# Cowbell.net
KiCad netlist of a schematic drawn in EAGLE
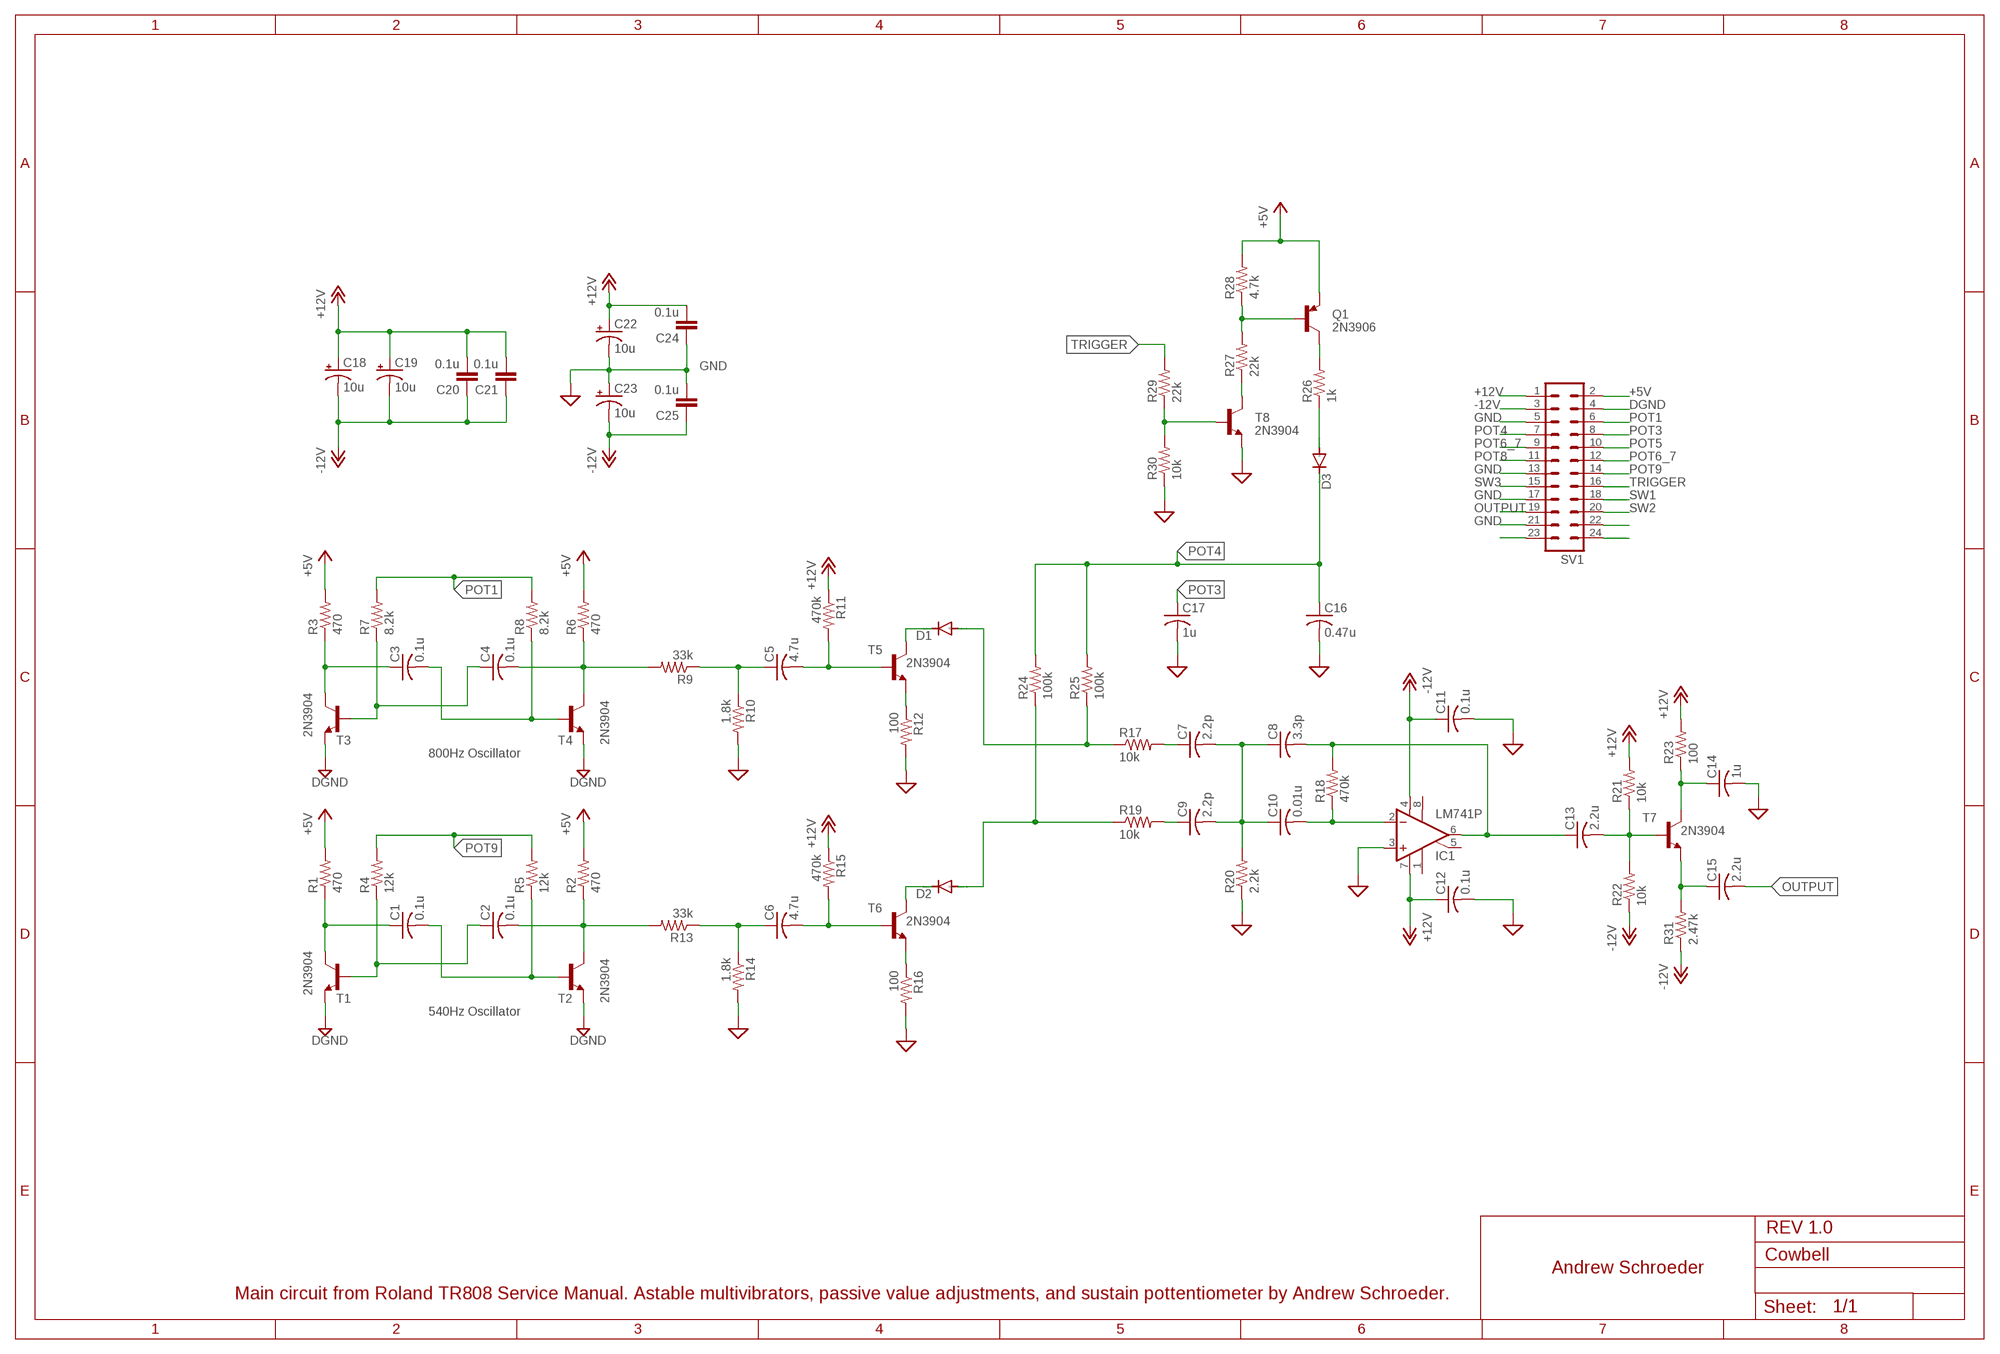
[diagram p0: schematic, sheet 1]

(export (version "E")
  (design (tool "Eeschema 10.0.6"))
  (components
    (comp (ref "C1")
      (value "0.1u")
      (footprint "eagle-import:C025-024X044")
      (libsource (lib "eagle-import") (part "C-US025-024X044"))
    )
    (comp (ref "C2")
      (value "0.1u")
      (footprint "eagle-import:C025-024X044")
      (libsource (lib "eagle-import") (part "C-US025-024X044"))
    )
    (comp (ref "C3")
      (value "0.1u")
      (footprint "eagle-import:C025-024X044")
      (libsource (lib "eagle-import") (part "C-US025-024X044"))
    )
    (comp (ref "C4")
      (value "0.1u")
      (footprint "eagle-import:C025-024X044")
      (libsource (lib "eagle-import") (part "C-US025-024X044"))
    )
    (comp (ref "C5")
      (value "4.7u")
      (footprint "eagle-import:C025-024X044")
      (libsource (lib "eagle-import") (part "C-US025-024X044"))
    )
    (comp (ref "C6")
      (value "4.7u")
      (footprint "eagle-import:C025-024X044")
      (libsource (lib "eagle-import") (part "C-US025-024X044"))
    )
    (comp (ref "C7")
      (value "2.2p")
      (footprint "eagle-import:C025-024X044")
      (libsource (lib "eagle-import") (part "C-US025-024X044"))
    )
    (comp (ref "C8")
      (value "3.3p")
      (footprint "eagle-import:C025-024X044")
      (libsource (lib "eagle-import") (part "C-US025-024X044"))
    )
    (comp (ref "C9")
      (value "2.2p")
      (footprint "eagle-import:C025-024X044")
      (libsource (lib "eagle-import") (part "C-US025-024X044"))
    )
    (comp (ref "C10")
      (value "0.01u")
      (footprint "eagle-import:C025-024X044")
      (libsource (lib "eagle-import") (part "C-US025-024X044"))
    )
    (comp (ref "C11")
      (value "0.1u")
      (footprint "eagle-import:C025-024X044")
      (libsource (lib "eagle-import") (part "C-US025-024X044"))
    )
    (comp (ref "C12")
      (value "0.1u")
      (footprint "eagle-import:C025-024X044")
      (libsource (lib "eagle-import") (part "C-US025-024X044"))
    )
    (comp (ref "C13")
      (value "2.2u")
      (footprint "eagle-import:C025-024X044")
      (libsource (lib "eagle-import") (part "C-US025-024X044"))
    )
    (comp (ref "C14")
      (value "1u")
      (footprint "eagle-import:C025-024X044")
      (libsource (lib "eagle-import") (part "C-US025-024X044"))
    )
    (comp (ref "C15")
      (value "2.2u")
      (footprint "eagle-import:C025-024X044")
      (libsource (lib "eagle-import") (part "C-US025-024X044"))
    )
    (comp (ref "C16")
      (value "0.47u")
      (footprint "eagle-import:C025-024X044")
      (libsource (lib "eagle-import") (part "C-US025-024X044"))
    )
    (comp (ref "C17")
      (value "1u")
      (footprint "eagle-import:C025-024X044")
      (libsource (lib "eagle-import") (part "C-US025-024X044"))
    )
    (comp (ref "C18")
      (value "10u")
      (footprint "eagle-import:E2,5-6")
      (libsource (lib "eagle-import") (part "CPOL-USE2.5-6"))
    )
    (comp (ref "C19")
      (value "10u")
      (footprint "eagle-import:E2,5-6")
      (libsource (lib "eagle-import") (part "CPOL-USE2.5-6"))
    )
    (comp (ref "C20")
      (value "0.1u")
      (footprint "eagle-import:C050-024X044")
      (libsource (lib "eagle-import") (part "C-EU050-024X044"))
    )
    (comp (ref "C21")
      (value "0.1u")
      (footprint "eagle-import:C050-024X044")
      (libsource (lib "eagle-import") (part "C-EU050-024X044"))
    )
    (comp (ref "C22")
      (value "10u")
      (footprint "eagle-import:E2,5-6")
      (libsource (lib "eagle-import") (part "CPOL-USE2.5-6"))
    )
    (comp (ref "C23")
      (value "10u")
      (footprint "eagle-import:E2,5-6")
      (libsource (lib "eagle-import") (part "CPOL-USE2.5-6"))
    )
    (comp (ref "C24")
      (value "0.1u")
      (footprint "eagle-import:C050-024X044")
      (libsource (lib "eagle-import") (part "C-EU050-024X044"))
    )
    (comp (ref "C25")
      (value "0.1u")
      (footprint "eagle-import:C050-024X044")
      (libsource (lib "eagle-import") (part "C-EU050-024X044"))
    )
    (comp (ref "D1")
      (value "1N4148DO35-7")
      (footprint "eagle-import:DO35-7")
      (libsource (lib "eagle-import") (part "1N4148DO35-7"))
    )
    (comp (ref "D2")
      (value "1N4148DO35-7")
      (footprint "eagle-import:DO35-7")
      (libsource (lib "eagle-import") (part "1N4148DO35-7"))
    )
    (comp (ref "D3")
      (value "1N4148DO35-7")
      (footprint "eagle-import:DO35-7")
      (libsource (lib "eagle-import") (part "1N4148DO35-7"))
    )
    (comp (ref "IC1")
      (value "LM741P")
      (footprint "eagle-import:DIL08")
      (libsource (lib "eagle-import") (part "741PLM"))
    )
    (comp (ref "Q1")
      (value "2N3906")
      (footprint "eagle-import:TO92")
      (libsource (lib "eagle-import") (part "2N3906"))
    )
    (comp (ref "R1")
      (value "470")
      (footprint "eagle-import:0207_7")
      (libsource (lib "eagle-import") (part "R-US_0207/7"))
    )
    (comp (ref "R2")
      (value "470")
      (footprint "eagle-import:0207_7")
      (libsource (lib "eagle-import") (part "R-US_0207/7"))
    )
    (comp (ref "R3")
      (value "470")
      (footprint "eagle-import:0207_7")
      (libsource (lib "eagle-import") (part "R-US_0207/7"))
    )
    (comp (ref "R4")
      (value "12k")
      (footprint "eagle-import:0207_7")
      (libsource (lib "eagle-import") (part "R-US_0207/7"))
    )
    (comp (ref "R5")
      (value "12k")
      (footprint "eagle-import:0207_7")
      (libsource (lib "eagle-import") (part "R-US_0207/7"))
    )
    (comp (ref "R6")
      (value "470")
      (footprint "eagle-import:0207_7")
      (libsource (lib "eagle-import") (part "R-US_0207/7"))
    )
    (comp (ref "R7")
      (value "8.2k")
      (footprint "eagle-import:0207_7")
      (libsource (lib "eagle-import") (part "R-US_0207/7"))
    )
    (comp (ref "R8")
      (value "8.2k")
      (footprint "eagle-import:0207_7")
      (libsource (lib "eagle-import") (part "R-US_0207/7"))
    )
    (comp (ref "R9")
      (value "33k")
      (footprint "eagle-import:0207_7")
      (libsource (lib "eagle-import") (part "R-US_0207/7"))
    )
    (comp (ref "R10")
      (value "1.8k")
      (footprint "eagle-import:0207_7")
      (libsource (lib "eagle-import") (part "R-US_0207/7"))
    )
    (comp (ref "R11")
      (value "470k")
      (footprint "eagle-import:0207_7")
      (libsource (lib "eagle-import") (part "R-US_0207/7"))
    )
    (comp (ref "R12")
      (value "100")
      (footprint "eagle-import:0207_7")
      (libsource (lib "eagle-import") (part "R-US_0207/7"))
    )
    (comp (ref "R13")
      (value "33k")
      (footprint "eagle-import:0207_7")
      (libsource (lib "eagle-import") (part "R-US_0207/7"))
    )
    (comp (ref "R14")
      (value "1.8k")
      (footprint "eagle-import:0207_7")
      (libsource (lib "eagle-import") (part "R-US_0207/7"))
    )
    (comp (ref "R15")
      (value "470k")
      (footprint "eagle-import:0207_7")
      (libsource (lib "eagle-import") (part "R-US_0207/7"))
    )
    (comp (ref "R16")
      (value "100")
      (footprint "eagle-import:0207_7")
      (libsource (lib "eagle-import") (part "R-US_0207/7"))
    )
    (comp (ref "R17")
      (value "10k")
      (footprint "eagle-import:0207_7")
      (libsource (lib "eagle-import") (part "R-US_0207/7"))
    )
    (comp (ref "R18")
      (value "470k")
      (footprint "eagle-import:0207_7")
      (libsource (lib "eagle-import") (part "R-US_0207/7"))
    )
    (comp (ref "R19")
      (value "10k")
      (footprint "eagle-import:0207_7")
      (libsource (lib "eagle-import") (part "R-US_0207/7"))
    )
    (comp (ref "R20")
      (value "2.2k")
      (footprint "eagle-import:0207_7")
      (libsource (lib "eagle-import") (part "R-US_0207/7"))
    )
    (comp (ref "R21")
      (value "10k")
      (footprint "eagle-import:0207_7")
      (libsource (lib "eagle-import") (part "R-US_0207/7"))
    )
    (comp (ref "R22")
      (value "10k")
      (footprint "eagle-import:0207_7")
      (libsource (lib "eagle-import") (part "R-US_0207/7"))
    )
    (comp (ref "R23")
      (value "100")
      (footprint "eagle-import:0207_7")
      (libsource (lib "eagle-import") (part "R-US_0207/7"))
    )
    (comp (ref "R24")
      (value "100k")
      (footprint "eagle-import:0207_7")
      (libsource (lib "eagle-import") (part "R-US_0207/7"))
    )
    (comp (ref "R25")
      (value "100k")
      (footprint "eagle-import:0207_7")
      (libsource (lib "eagle-import") (part "R-US_0207/7"))
    )
    (comp (ref "R26")
      (value "1k")
      (footprint "eagle-import:0207_7")
      (libsource (lib "eagle-import") (part "R-US_0207/7"))
    )
    (comp (ref "R27")
      (value "22k")
      (footprint "eagle-import:0207_7")
      (libsource (lib "eagle-import") (part "R-US_0207/7"))
    )
    (comp (ref "R28")
      (value "4.7k")
      (footprint "eagle-import:0207_7")
      (libsource (lib "eagle-import") (part "R-US_0207/7"))
    )
    (comp (ref "R29")
      (value "22k")
      (footprint "eagle-import:0207_7")
      (libsource (lib "eagle-import") (part "R-US_0207/7"))
    )
    (comp (ref "R30")
      (value "10k")
      (footprint "eagle-import:0207_7")
      (libsource (lib "eagle-import") (part "R-US_0207/7"))
    )
    (comp (ref "R31")
      (value "2.47k")
      (footprint "eagle-import:0207_7")
      (libsource (lib "eagle-import") (part "R-US_0207/7"))
    )
    (comp (ref "SV1")
      (value "MA12-2")
      (footprint "eagle-import:MA12-2")
      (libsource (lib "eagle-import") (part "MA12-2"))
    )
    (comp (ref "T1")
      (value "2N3904")
      (footprint "eagle-import:TO92")
      (libsource (lib "eagle-import") (part "2N3904"))
    )
    (comp (ref "T2")
      (value "2N3904")
      (footprint "eagle-import:TO92")
      (libsource (lib "eagle-import") (part "2N3904"))
    )
    (comp (ref "T3")
      (value "2N3904")
      (footprint "eagle-import:TO92")
      (libsource (lib "eagle-import") (part "2N3904"))
    )
    (comp (ref "T4")
      (value "2N3904")
      (footprint "eagle-import:TO92")
      (libsource (lib "eagle-import") (part "2N3904"))
    )
    (comp (ref "T5")
      (value "2N3904")
      (footprint "eagle-import:TO92")
      (libsource (lib "eagle-import") (part "2N3904"))
    )
    (comp (ref "T6")
      (value "2N3904")
      (footprint "eagle-import:TO92")
      (libsource (lib "eagle-import") (part "2N3904"))
    )
    (comp (ref "T7")
      (value "2N3904")
      (footprint "eagle-import:TO92")
      (libsource (lib "eagle-import") (part "2N3904"))
    )
    (comp (ref "T8")
      (value "2N3904")
      (footprint "eagle-import:TO92")
      (libsource (lib "eagle-import") (part "2N3904"))
    )
  )
  (nets
    (net (code "1") (name "+5V") (class "Default")
      (node (ref "Q1") (pin "3") (pinfunction "E_3") (pintype "passive"))
      (node (ref "R1") (pin "2") (pinfunction "2_2") (pintype "passive"))
      (node (ref "R2") (pin "2") (pinfunction "2_2") (pintype "passive"))
      (node (ref "R28") (pin "2") (pinfunction "2_2") (pintype "passive"))
      (node (ref "R3") (pin "2") (pinfunction "2_2") (pintype "passive"))
      (node (ref "R6") (pin "2") (pinfunction "2_2") (pintype "passive"))
      (node (ref "SV1") (pin "2") (pinfunction "2_2") (pintype "passive"))
    )
    (net (code "2") (name "+12V") (class "Default")
      (node (ref "C12") (pin "1") (pinfunction "1_1") (pintype "passive"))
      (node (ref "C18") (pin "+") (pinfunction "+_+") (pintype "passive"))
      (node (ref "C19") (pin "+") (pinfunction "+_+") (pintype "passive"))
      (node (ref "C20") (pin "2") (pinfunction "2_2") (pintype "passive"))
      (node (ref "C21") (pin "2") (pinfunction "2_2") (pintype "passive"))
      (node (ref "C22") (pin "+") (pinfunction "+_+") (pintype "passive"))
      (node (ref "C24") (pin "2") (pinfunction "2_2") (pintype "passive"))
      (node (ref "IC1") (pin "7") (pinfunction "V+_7") (pintype "power_in"))
      (node (ref "R11") (pin "1") (pinfunction "1_1") (pintype "passive"))
      (node (ref "R15") (pin "1") (pinfunction "1_1") (pintype "passive"))
      (node (ref "R21") (pin "2") (pinfunction "2_2") (pintype "passive"))
      (node (ref "R23") (pin "2") (pinfunction "2_2") (pintype "passive"))
      (node (ref "SV1") (pin "1") (pinfunction "1_1") (pintype "passive"))
    )
    (net (code "3") (name "-12V") (class "Default")
      (node (ref "C11") (pin "1") (pinfunction "1_1") (pintype "passive"))
      (node (ref "C18") (pin "-") (pinfunction "-_-") (pintype "passive"))
      (node (ref "C19") (pin "-") (pinfunction "-_-") (pintype "passive"))
      (node (ref "C20") (pin "1") (pinfunction "1_1") (pintype "passive"))
      (node (ref "C21") (pin "1") (pinfunction "1_1") (pintype "passive"))
      (node (ref "C23") (pin "-") (pinfunction "-_-") (pintype "passive"))
      (node (ref "C25") (pin "1") (pinfunction "1_1") (pintype "passive"))
      (node (ref "IC1") (pin "4") (pinfunction "V-_4") (pintype "power_in"))
      (node (ref "R22") (pin "1") (pinfunction "1_1") (pintype "passive"))
      (node (ref "R31") (pin "1") (pinfunction "1_1") (pintype "passive"))
      (node (ref "SV1") (pin "3") (pinfunction "3_3") (pintype "passive"))
    )
    (net (code "4") (name "/POT5") (class "Default")
      (node (ref "SV1") (pin "10") (pinfunction "10_10") (pintype "passive"))
    )
    (net (code "5") (name "/POT6_7") (class "Default")
      (node (ref "SV1") (pin "12") (pinfunction "12_12") (pintype "passive"))
      (node (ref "SV1") (pin "9") (pinfunction "9_9") (pintype "passive"))
    )
    (net (code "6") (name "/POT8") (class "Default")
      (node (ref "SV1") (pin "11") (pinfunction "11_11") (pintype "passive"))
    )
    (net (code "7") (name "/SW1") (class "Default")
      (node (ref "SV1") (pin "18") (pinfunction "18_18") (pintype "passive"))
    )
    (net (code "8") (name "/SW2") (class "Default")
      (node (ref "SV1") (pin "20") (pinfunction "20_20") (pintype "passive"))
    )
    (net (code "9") (name "/SW3") (class "Default")
      (node (ref "SV1") (pin "15") (pinfunction "15_15") (pintype "passive"))
    )
    (net (code "10") (name "DGND") (class "Default")
      (node (ref "SV1") (pin "4") (pinfunction "4_4") (pintype "passive"))
      (node (ref "T1") (pin "3") (pinfunction "E_3") (pintype "passive"))
      (node (ref "T2") (pin "3") (pinfunction "E_3") (pintype "passive"))
      (node (ref "T3") (pin "3") (pinfunction "E_3") (pintype "passive"))
      (node (ref "T4") (pin "3") (pinfunction "E_3") (pintype "passive"))
    )
    (net (code "11") (name "Net-(C5-Pad1)") (class "Default")
      (node (ref "C5") (pin "1") (pinfunction "1_1") (pintype "passive"))
      (node (ref "R10") (pin "1") (pinfunction "1_1") (pintype "passive"))
      (node (ref "R9") (pin "1") (pinfunction "1_1") (pintype "passive"))
    )
    (net (code "12") (name "Net-(C6-Pad1)") (class "Default")
      (node (ref "C6") (pin "1") (pinfunction "1_1") (pintype "passive"))
      (node (ref "R13") (pin "1") (pinfunction "1_1") (pintype "passive"))
      (node (ref "R14") (pin "1") (pinfunction "1_1") (pintype "passive"))
    )
    (net (code "13") (name "Net-(C7-Pad1)") (class "Default")
      (node (ref "C7") (pin "1") (pinfunction "1_1") (pintype "passive"))
      (node (ref "R17") (pin "2") (pinfunction "2_2") (pintype "passive"))
    )
    (net (code "14") (name "Net-(C9-Pad1)") (class "Default")
      (node (ref "C9") (pin "1") (pinfunction "1_1") (pintype "passive"))
      (node (ref "R19") (pin "2") (pinfunction "2_2") (pintype "passive"))
    )
    (net (code "15") (name "Net-(C10-Pad1)") (class "Default")
      (node (ref "C10") (pin "1") (pinfunction "1_1") (pintype "passive"))
      (node (ref "C7") (pin "2") (pinfunction "2_2") (pintype "passive"))
      (node (ref "C8") (pin "1") (pinfunction "1_1") (pintype "passive"))
      (node (ref "C9") (pin "2") (pinfunction "2_2") (pintype "passive"))
      (node (ref "R20") (pin "2") (pinfunction "2_2") (pintype "passive"))
    )
    (net (code "16") (name "Net-(D1-PadA)") (class "Default")
      (node (ref "D1") (pin "A") (pinfunction "A_A") (pintype "passive"))
      (node (ref "R17") (pin "1") (pinfunction "1_1") (pintype "passive"))
      (node (ref "R25") (pin "1") (pinfunction "1_1") (pintype "passive"))
    )
    (net (code "17") (name "Net-(D2-PadA)") (class "Default")
      (node (ref "D2") (pin "A") (pinfunction "A_A") (pintype "passive"))
      (node (ref "R19") (pin "1") (pinfunction "1_1") (pintype "passive"))
      (node (ref "R24") (pin "1") (pinfunction "1_1") (pintype "passive"))
    )
    (net (code "18") (name "Net-(D3-PadA)") (class "Default")
      (node (ref "D3") (pin "A") (pinfunction "A_A") (pintype "passive"))
      (node (ref "R26") (pin "1") (pinfunction "1_1") (pintype "passive"))
    )
    (net (code "19") (name "Net-(IC1--IN)") (class "Default")
      (node (ref "C10") (pin "2") (pinfunction "2_2") (pintype "passive"))
      (node (ref "IC1") (pin "2") (pinfunction "-IN_2") (pintype "input"))
      (node (ref "R18") (pin "1") (pinfunction "1_1") (pintype "passive"))
    )
    (net (code "20") (name "Net-(IC1-OUT)") (class "Default")
      (node (ref "C13") (pin "1") (pinfunction "1_1") (pintype "passive"))
      (node (ref "C8") (pin "2") (pinfunction "2_2") (pintype "passive"))
      (node (ref "IC1") (pin "6") (pinfunction "OUT_6") (pintype "output"))
      (node (ref "R18") (pin "2") (pinfunction "2_2") (pintype "passive"))
    )
    (net (code "21") (name "Net-(Q1-B)") (class "Default")
      (node (ref "Q1") (pin "2") (pinfunction "B_2") (pintype "passive"))
      (node (ref "R27") (pin "2") (pinfunction "2_2") (pintype "passive"))
      (node (ref "R28") (pin "1") (pinfunction "1_1") (pintype "passive"))
    )
    (net (code "22") (name "Net-(Q1-C)") (class "Default")
      (node (ref "Q1") (pin "1") (pinfunction "C_1") (pintype "passive"))
      (node (ref "R26") (pin "2") (pinfunction "2_2") (pintype "passive"))
    )
    (net (code "23") (name "Net-(T1-B)") (class "Default")
      (node (ref "C2") (pin "1") (pinfunction "1_1") (pintype "passive"))
      (node (ref "R4") (pin "1") (pinfunction "1_1") (pintype "passive"))
      (node (ref "T1") (pin "2") (pinfunction "B_2") (pintype "passive"))
    )
    (net (code "24") (name "Net-(T1-C)") (class "Default")
      (node (ref "C1") (pin "1") (pinfunction "1_1") (pintype "passive"))
      (node (ref "R1") (pin "1") (pinfunction "1_1") (pintype "passive"))
      (node (ref "T1") (pin "1") (pinfunction "C_1") (pintype "passive"))
    )
    (net (code "25") (name "Net-(T2-B)") (class "Default")
      (node (ref "C1") (pin "2") (pinfunction "2_2") (pintype "passive"))
      (node (ref "R5") (pin "1") (pinfunction "1_1") (pintype "passive"))
      (node (ref "T2") (pin "2") (pinfunction "B_2") (pintype "passive"))
    )
    (net (code "26") (name "Net-(T2-C)") (class "Default")
      (node (ref "C2") (pin "2") (pinfunction "2_2") (pintype "passive"))
      (node (ref "R13") (pin "2") (pinfunction "2_2") (pintype "passive"))
      (node (ref "R2") (pin "1") (pinfunction "1_1") (pintype "passive"))
      (node (ref "T2") (pin "1") (pinfunction "C_1") (pintype "passive"))
    )
    (net (code "27") (name "Net-(T3-B)") (class "Default")
      (node (ref "C4") (pin "1") (pinfunction "1_1") (pintype "passive"))
      (node (ref "R7") (pin "1") (pinfunction "1_1") (pintype "passive"))
      (node (ref "T3") (pin "2") (pinfunction "B_2") (pintype "passive"))
    )
    (net (code "28") (name "Net-(T3-C)") (class "Default")
      (node (ref "C3") (pin "1") (pinfunction "1_1") (pintype "passive"))
      (node (ref "R3") (pin "1") (pinfunction "1_1") (pintype "passive"))
      (node (ref "T3") (pin "1") (pinfunction "C_1") (pintype "passive"))
    )
    (net (code "29") (name "Net-(T4-B)") (class "Default")
      (node (ref "C3") (pin "2") (pinfunction "2_2") (pintype "passive"))
      (node (ref "R8") (pin "1") (pinfunction "1_1") (pintype "passive"))
      (node (ref "T4") (pin "2") (pinfunction "B_2") (pintype "passive"))
    )
    (net (code "30") (name "Net-(T4-C)") (class "Default")
      (node (ref "C4") (pin "2") (pinfunction "2_2") (pintype "passive"))
      (node (ref "R6") (pin "1") (pinfunction "1_1") (pintype "passive"))
      (node (ref "R9") (pin "2") (pinfunction "2_2") (pintype "passive"))
      (node (ref "T4") (pin "1") (pinfunction "C_1") (pintype "passive"))
    )
    (net (code "31") (name "Net-(T5-B)") (class "Default")
      (node (ref "C5") (pin "2") (pinfunction "2_2") (pintype "passive"))
      (node (ref "R11") (pin "2") (pinfunction "2_2") (pintype "passive"))
      (node (ref "T5") (pin "2") (pinfunction "B_2") (pintype "passive"))
    )
    (net (code "32") (name "Net-(T5-C)") (class "Default")
      (node (ref "D1") (pin "C") (pinfunction "C_C") (pintype "passive"))
      (node (ref "T5") (pin "1") (pinfunction "C_1") (pintype "passive"))
    )
    (net (code "33") (name "Net-(T5-E)") (class "Default")
      (node (ref "R12") (pin "1") (pinfunction "1_1") (pintype "passive"))
      (node (ref "T5") (pin "3") (pinfunction "E_3") (pintype "passive"))
    )
    (net (code "34") (name "Net-(T6-B)") (class "Default")
      (node (ref "C6") (pin "2") (pinfunction "2_2") (pintype "passive"))
      (node (ref "R15") (pin "2") (pinfunction "2_2") (pintype "passive"))
      (node (ref "T6") (pin "2") (pinfunction "B_2") (pintype "passive"))
    )
    (net (code "35") (name "Net-(T6-C)") (class "Default")
      (node (ref "D2") (pin "C") (pinfunction "C_C") (pintype "passive"))
      (node (ref "T6") (pin "1") (pinfunction "C_1") (pintype "passive"))
    )
    (net (code "36") (name "Net-(T6-E)") (class "Default")
      (node (ref "R16") (pin "1") (pinfunction "1_1") (pintype "passive"))
      (node (ref "T6") (pin "3") (pinfunction "E_3") (pintype "passive"))
    )
    (net (code "37") (name "Net-(T7-B)") (class "Default")
      (node (ref "C13") (pin "2") (pinfunction "2_2") (pintype "passive"))
      (node (ref "R21") (pin "1") (pinfunction "1_1") (pintype "passive"))
      (node (ref "R22") (pin "2") (pinfunction "2_2") (pintype "passive"))
      (node (ref "T7") (pin "2") (pinfunction "B_2") (pintype "passive"))
    )
    (net (code "38") (name "Net-(T7-C)") (class "Default")
      (node (ref "C14") (pin "1") (pinfunction "1_1") (pintype "passive"))
      (node (ref "R23") (pin "1") (pinfunction "1_1") (pintype "passive"))
      (node (ref "T7") (pin "1") (pinfunction "C_1") (pintype "passive"))
    )
    (net (code "39") (name "Net-(T7-E)") (class "Default")
      (node (ref "C15") (pin "1") (pinfunction "1_1") (pintype "passive"))
      (node (ref "R31") (pin "2") (pinfunction "2_2") (pintype "passive"))
      (node (ref "T7") (pin "3") (pinfunction "E_3") (pintype "passive"))
    )
    (net (code "40") (name "Net-(T8-B)") (class "Default")
      (node (ref "R29") (pin "1") (pinfunction "1_1") (pintype "passive"))
      (node (ref "R30") (pin "2") (pinfunction "2_2") (pintype "passive"))
      (node (ref "T8") (pin "2") (pinfunction "B_2") (pintype "passive"))
    )
    (net (code "41") (name "Net-(T8-C)") (class "Default")
      (node (ref "R27") (pin "1") (pinfunction "1_1") (pintype "passive"))
      (node (ref "T8") (pin "1") (pinfunction "C_1") (pintype "passive"))
    )
    (net (code "42") (name "OUTPUT") (class "Default")
      (node (ref "C15") (pin "2") (pinfunction "2_2") (pintype "passive"))
      (node (ref "SV1") (pin "19") (pinfunction "19_19") (pintype "passive"))
    )
    (net (code "43") (name "POT1") (class "Default")
      (node (ref "R7") (pin "2") (pinfunction "2_2") (pintype "passive"))
      (node (ref "R8") (pin "2") (pinfunction "2_2") (pintype "passive"))
      (node (ref "SV1") (pin "6") (pinfunction "6_6") (pintype "passive"))
    )
    (net (code "44") (name "POT3") (class "Default")
      (node (ref "C17") (pin "1") (pinfunction "1_1") (pintype "passive"))
      (node (ref "SV1") (pin "8") (pinfunction "8_8") (pintype "passive"))
    )
    (net (code "45") (name "POT4") (class "Default")
      (node (ref "C16") (pin "1") (pinfunction "1_1") (pintype "passive"))
      (node (ref "D3") (pin "C") (pinfunction "C_C") (pintype "passive"))
      (node (ref "R24") (pin "2") (pinfunction "2_2") (pintype "passive"))
      (node (ref "R25") (pin "2") (pinfunction "2_2") (pintype "passive"))
      (node (ref "SV1") (pin "7") (pinfunction "7_7") (pintype "passive"))
    )
    (net (code "46") (name "POT9") (class "Default")
      (node (ref "R4") (pin "2") (pinfunction "2_2") (pintype "passive"))
      (node (ref "R5") (pin "2") (pinfunction "2_2") (pintype "passive"))
      (node (ref "SV1") (pin "14") (pinfunction "14_14") (pintype "passive"))
    )
    (net (code "47") (name "SUP") (class "Default")
      (node (ref "C11") (pin "2") (pinfunction "2_2") (pintype "passive"))
      (node (ref "C12") (pin "2") (pinfunction "2_2") (pintype "passive"))
      (node (ref "C14") (pin "2") (pinfunction "2_2") (pintype "passive"))
      (node (ref "C16") (pin "2") (pinfunction "2_2") (pintype "passive"))
      (node (ref "C17") (pin "2") (pinfunction "2_2") (pintype "passive"))
      (node (ref "C22") (pin "-") (pinfunction "-_-") (pintype "passive"))
      (node (ref "C23") (pin "+") (pinfunction "+_+") (pintype "passive"))
      (node (ref "C24") (pin "1") (pinfunction "1_1") (pintype "passive"))
      (node (ref "C25") (pin "2") (pinfunction "2_2") (pintype "passive"))
      (node (ref "IC1") (pin "3") (pinfunction "+IN_3") (pintype "input"))
      (node (ref "R10") (pin "2") (pinfunction "2_2") (pintype "passive"))
      (node (ref "R12") (pin "2") (pinfunction "2_2") (pintype "passive"))
      (node (ref "R14") (pin "2") (pinfunction "2_2") (pintype "passive"))
      (node (ref "R16") (pin "2") (pinfunction "2_2") (pintype "passive"))
      (node (ref "R20") (pin "1") (pinfunction "1_1") (pintype "passive"))
      (node (ref "R30") (pin "1") (pinfunction "1_1") (pintype "passive"))
      (node (ref "SV1") (pin "13") (pinfunction "13_13") (pintype "passive"))
      (node (ref "SV1") (pin "17") (pinfunction "17_17") (pintype "passive"))
      (node (ref "SV1") (pin "21") (pinfunction "21_21") (pintype "passive"))
      (node (ref "SV1") (pin "5") (pinfunction "5_5") (pintype "passive"))
      (node (ref "T8") (pin "3") (pinfunction "E_3") (pintype "passive"))
    )
    (net (code "48") (name "TRIGGER") (class "Default")
      (node (ref "R29") (pin "2") (pinfunction "2_2") (pintype "passive"))
      (node (ref "SV1") (pin "16") (pinfunction "16_16") (pintype "passive"))
    )
    (net (code "49") (name "unconnected-(IC1-ON1-Pad1)") (class "Default")
      (node (ref "IC1") (pin "1") (pinfunction "ON1_1") (pintype "passive"))
    )
    (net (code "50") (name "unconnected-(IC1-ON2-Pad5)") (class "Default")
      (node (ref "IC1") (pin "5") (pinfunction "ON2_5") (pintype "passive"))
    )
    (net (code "51") (name "unconnected-(IC1-OPT-Pad8)") (class "Default")
      (node (ref "IC1") (pin "8") (pinfunction "OPT_8") (pintype "passive"))
    )
    (net (code "52") (name "unconnected-(SV1-Pad22)") (class "Default")
      (node (ref "SV1") (pin "22") (pinfunction "22_22") (pintype "passive"))
    )
    (net (code "53") (name "unconnected-(SV1-Pad23)") (class "Default")
      (node (ref "SV1") (pin "23") (pinfunction "23_23") (pintype "passive"))
    )
    (net (code "54") (name "unconnected-(SV1-Pad24)") (class "Default")
      (node (ref "SV1") (pin "24") (pinfunction "24_24") (pintype "passive"))
    )
  )
)
